# Sheet2.net
KiCad netlist of a schematic drawn in Altium Designer
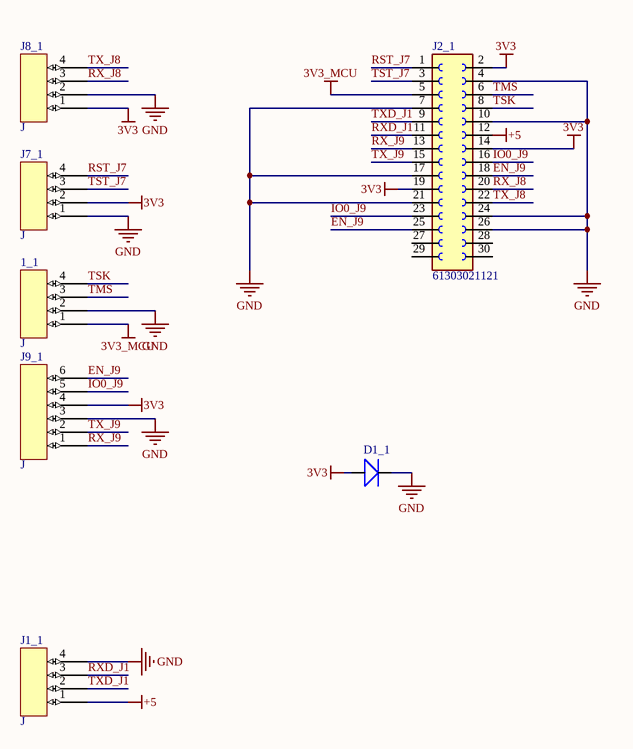
[diagram p0: Sheet2.SchDoc]

(export (version "E")
  (design (tool "Eeschema 10.0.6"))
  (components
    (comp (ref "1_1") (value "J") (footprint "J4") (libsource (lib "Schlib2") (part "J4")))
    (comp (ref "D1_1")
      (value "SMD-DIODE-SWITCHING-75V-150MA(D1206)")
      (footprint "LED-1206")
      (description "304040005")
      (fields (field (name "MF") "{'manufacturer': u'Bourns'}"))
      (libsource (lib "CD1206-S01575") (part "SMD-DIODE-SWITCHING-75V-150MA(D1206)"))
    )
    (comp (ref "J1_1") (value "J") (footprint "J4") (libsource (lib "Schlib2") (part "J4")))
    (comp (ref "J2_1")
      (value "61303021121")
      (footprint "61303021121:61303021121")
      (fields (field (name "MF") "{'manufacturer': u'Wurth Elektronik'}"))
      (libsource (lib "*") (part "61303021121"))
    )
    (comp (ref "J7_1") (value "J") (footprint "J4") (libsource (lib "Schlib2") (part "J4")))
    (comp (ref "J8_1") (value "J") (footprint "J4") (libsource (lib "Schlib2") (part "J4")))
    (comp (ref "J9_1") (value "J") (footprint "J6") (libsource (lib "Schlib1") (part "J6")))
  )
  (nets
    (net (code "1") (name "+5") (class "Default")
      (node (ref "J1_1") (pin "1") (pintype "bidirectional"))
      (node (ref "J2_1") (pin "12") (pinfunction "25_12") (pintype "passive"))
    )
    (net (code "2") (name "/EN_J9") (class "Default")
      (node (ref "J2_1") (pin "18") (pinfunction "22_18") (pintype "passive"))
      (node (ref "J2_1") (pin "25") (pinfunction "13_25") (pintype "passive"))
      (node (ref "J9_1") (pin "6") (pintype "bidirectional"))
    )
    (net (code "3") (name "/IO0_J9") (class "Default")
      (node (ref "J2_1") (pin "16") (pinfunction "23_16") (pintype "passive"))
      (node (ref "J2_1") (pin "23") (pinfunction "12_23") (pintype "passive"))
      (node (ref "J9_1") (pin "5") (pintype "bidirectional"))
    )
    (net (code "4") (name "/RST_J7") (class "Default")
      (node (ref "J2_1") (pin "1") (pinfunction "1_1") (pintype "passive"))
      (node (ref "J7_1") (pin "4") (pintype "bidirectional"))
    )
    (net (code "5") (name "/RXD_J1") (class "Default")
      (node (ref "J1_1") (pin "3") (pintype "bidirectional"))
      (node (ref "J2_1") (pin "11") (pinfunction "6_11") (pintype "passive"))
    )
    (net (code "6") (name "/RX_J8") (class "Default")
      (node (ref "J2_1") (pin "20") (pinfunction "21_20") (pintype "passive"))
      (node (ref "J8_1") (pin "3") (pintype "bidirectional"))
    )
    (net (code "7") (name "/RX_J9") (class "Default")
      (node (ref "J2_1") (pin "13") (pinfunction "7_13") (pintype "passive"))
      (node (ref "J9_1") (pin "1") (pintype "bidirectional"))
    )
    (net (code "8") (name "/TMS") (class "Default")
      (node (ref "1_1") (pin "3") (pintype "bidirectional"))
      (node (ref "J2_1") (pin "6") (pinfunction "28_6") (pintype "passive"))
    )
    (net (code "9") (name "/TSK") (class "Default")
      (node (ref "1_1") (pin "4") (pintype "bidirectional"))
      (node (ref "J2_1") (pin "8") (pinfunction "27_8") (pintype "passive"))
    )
    (net (code "10") (name "/TST_J7") (class "Default")
      (node (ref "J2_1") (pin "3") (pinfunction "2_3") (pintype "passive"))
      (node (ref "J7_1") (pin "3") (pintype "bidirectional"))
    )
    (net (code "11") (name "/TXD_J1") (class "Default")
      (node (ref "J1_1") (pin "2") (pintype "bidirectional"))
      (node (ref "J2_1") (pin "9") (pinfunction "5_9") (pintype "passive"))
    )
    (net (code "12") (name "/TX_J8") (class "Default")
      (node (ref "J2_1") (pin "22") (pinfunction "20_22") (pintype "passive"))
      (node (ref "J8_1") (pin "4") (pintype "bidirectional"))
    )
    (net (code "13") (name "/TX_J9") (class "Default")
      (node (ref "J2_1") (pin "15") (pinfunction "8_15") (pintype "passive"))
      (node (ref "J9_1") (pin "2") (pintype "bidirectional"))
    )
    (net (code "14") (name "3V3") (class "Default")
      (node (ref "D1_1") (pin "POS") (pinfunction "POS_POS") (pintype "passive"))
      (node (ref "J2_1") (pin "14") (pinfunction "24_14") (pintype "passive"))
      (node (ref "J2_1") (pin "19") (pinfunction "10_19") (pintype "passive"))
      (node (ref "J2_1") (pin "2") (pinfunction "30_2") (pintype "passive"))
      (node (ref "J7_1") (pin "2") (pintype "bidirectional"))
      (node (ref "J8_1") (pin "1") (pintype "bidirectional"))
      (node (ref "J9_1") (pin "4") (pintype "bidirectional"))
    )
    (net (code "15") (name "3V3_MCU") (class "Default")
      (node (ref "1_1") (pin "1") (pintype "bidirectional"))
      (node (ref "J2_1") (pin "5") (pinfunction "3_5") (pintype "passive"))
    )
    (net (code "16") (name "GND") (class "Default")
      (node (ref "1_1") (pin "2") (pintype "bidirectional"))
      (node (ref "D1_1") (pin "NEG") (pinfunction "NEG_NEG") (pintype "passive"))
      (node (ref "J1_1") (pin "4") (pintype "bidirectional"))
      (node (ref "J2_1") (pin "10") (pinfunction "26_10") (pintype "passive"))
      (node (ref "J2_1") (pin "17") (pinfunction "9_17") (pintype "passive"))
      (node (ref "J2_1") (pin "21") (pinfunction "11_21") (pintype "passive"))
      (node (ref "J2_1") (pin "24") (pinfunction "19_24") (pintype "passive"))
      (node (ref "J2_1") (pin "26") (pinfunction "18_26") (pintype "passive"))
      (node (ref "J2_1") (pin "4") (pinfunction "29_4") (pintype "passive"))
      (node (ref "J2_1") (pin "7") (pinfunction "4_7") (pintype "passive"))
      (node (ref "J7_1") (pin "1") (pintype "bidirectional"))
      (node (ref "J8_1") (pin "2") (pintype "bidirectional"))
      (node (ref "J9_1") (pin "3") (pintype "bidirectional"))
    )
    (net (code "17") (name "unconnected-(J2_1-14-Pad27)") (class "Default")
      (node (ref "J2_1") (pin "27") (pinfunction "14_27") (pintype "passive"))
    )
    (net (code "18") (name "unconnected-(J2_1-15-Pad29)") (class "Default")
      (node (ref "J2_1") (pin "29") (pinfunction "15_29") (pintype "passive"))
    )
    (net (code "19") (name "unconnected-(J2_1-16-Pad30)") (class "Default")
      (node (ref "J2_1") (pin "30") (pinfunction "16_30") (pintype "passive"))
    )
    (net (code "20") (name "unconnected-(J2_1-17-Pad28)") (class "Default")
      (node (ref "J2_1") (pin "28") (pinfunction "17_28") (pintype "passive"))
    )
  )
)
